# Accelerometre.net
KiCad netlist of a schematic drawn in Altium Designer
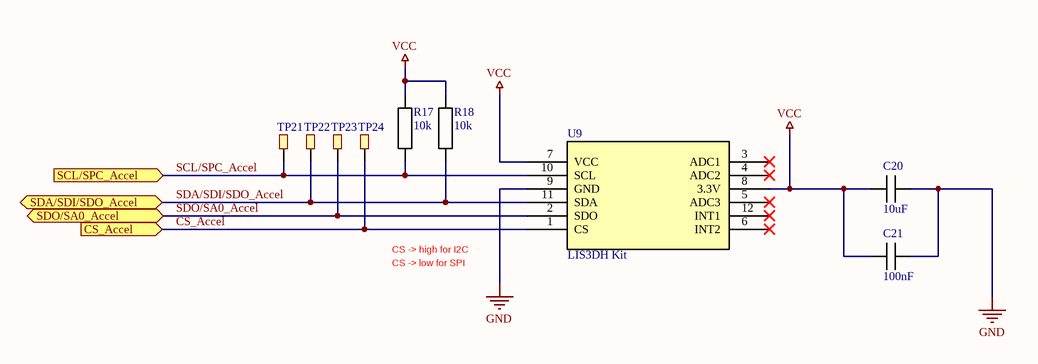
[diagram p0: Accelerometre.SchDoc]

(export (version "E")
  (design (tool "Eeschema 10.0.6"))
  (components
    (comp (ref "C20")
      (value "10uF")
      (footprint "CAPC1608X08M")
      (description "CAPC 10uF X5R 10V 20% 1608 (0603 INCH)")
      (fields (field (name "TOLERANCE") "±20%") (field (name "MANUFACTURER") "TDK"))
      (libsource (lib "ETML-ES") (part "CAP"))
    )
    (comp (ref "C21")
      (value "100nF")
      (footprint "CAPC1608X08M")
      (description "CAPC 100nF X7R 50V 10% 1608 (0603 INCH)")
      (fields (field (name "VOLTAGE") "50V") (field (name "MANUFACTURER") "TDK"))
      (libsource (lib "ETML-ES") (part "CAP"))
    )
    (comp (ref "R17")
      (value "10k")
      (footprint "RESC1608X06M")
      (description "RES 10kohm  ±1% 0.1W  1608 (0603 INCH)")
      (fields (field (name "TOLERANCE") "±1%") (field (name "VOLTAGE") "75V"))
      (libsource (lib "ETML-ES") (part "RES"))
    )
    (comp (ref "R18")
      (value "10k")
      (footprint "RESC1608X06M")
      (description "RES 10kohm  ±1% 0.1W  1608 (0603 INCH)")
      (fields (field (name "TOLERANCE") "±1%") (field (name "VOLTAGE") "75V"))
      (libsource (lib "ETML-ES") (part "RES"))
    )
    (comp (ref "TP21")
      (value "TestPoint")
      (footprint "KEYSTONE_5019")
      (libsource (lib "Schlib1") (part "TestPoint"))
    )
    (comp (ref "TP22")
      (value "TestPoint")
      (footprint "KEYSTONE_5019")
      (libsource (lib "Schlib1") (part "TestPoint"))
    )
    (comp (ref "TP23")
      (value "TestPoint")
      (footprint "KEYSTONE_5019")
      (libsource (lib "Schlib1") (part "TestPoint"))
    )
    (comp (ref "TP24")
      (value "TestPoint")
      (footprint "KEYSTONE_5019")
      (libsource (lib "Schlib1") (part "TestPoint"))
    )
    (comp (ref "U9")
      (value "LIS3DH Kit")
      (footprint "LIS3DH_Kit")
      (libsource (lib "Schlib1") (part "LIS3DH Kit"))
    )
  )
  (nets
    (net (code "1") (name "/CS_Accel") (class "Default")
      (node (ref "TP24") (pin "1") (pinfunction "1_1") (pintype "passive"))
      (node (ref "U9") (pin "1") (pinfunction "CS_1") (pintype "passive"))
    )
    (net (code "2") (name "/SCL{slash}SPC_Accel") (class "Default")
      (node (ref "R17") (pin "1") (pinfunction "1_1") (pintype "passive"))
      (node (ref "TP21") (pin "1") (pinfunction "1_1") (pintype "passive"))
      (node (ref "U9") (pin "10") (pinfunction "SCL_10") (pintype "passive"))
    )
    (net (code "3") (name "/SDA{slash}SDI{slash}SDO_Accel") (class "Default")
      (node (ref "R18") (pin "1") (pinfunction "1_1") (pintype "passive"))
      (node (ref "TP22") (pin "1") (pinfunction "1_1") (pintype "passive"))
      (node (ref "U9") (pin "11") (pinfunction "SDA_11") (pintype "passive"))
    )
    (net (code "4") (name "/SDO{slash}SA0_Accel") (class "Default")
      (node (ref "TP23") (pin "1") (pinfunction "1_1") (pintype "passive"))
      (node (ref "U9") (pin "2") (pinfunction "SDO_2") (pintype "passive"))
    )
    (net (code "5") (name "GND") (class "Default")
      (node (ref "C20") (pin "2") (pinfunction "2_2") (pintype "passive"))
      (node (ref "C21") (pin "2") (pinfunction "2_2") (pintype "passive"))
      (node (ref "U9") (pin "9") (pinfunction "GND_9") (pintype "passive"))
    )
    (net (code "6") (name "VCC") (class "Default")
      (node (ref "C20") (pin "1") (pinfunction "1_1") (pintype "passive"))
      (node (ref "C21") (pin "1") (pinfunction "1_1") (pintype "passive"))
      (node (ref "R17") (pin "2") (pinfunction "2_2") (pintype "passive"))
      (node (ref "R18") (pin "2") (pinfunction "2_2") (pintype "passive"))
      (node (ref "U9") (pin "7") (pinfunction "VCC_7") (pintype "passive"))
      (node (ref "U9") (pin "8") (pinfunction "3.3V_8") (pintype "passive"))
    )
    (net (code "7") (name "unconnected-(U9-ADC1-Pad3)") (class "Default")
      (node (ref "U9") (pin "3") (pinfunction "ADC1_3") (pintype "passive+no_connect"))
    )
    (net (code "8") (name "unconnected-(U9-ADC2-Pad4)") (class "Default")
      (node (ref "U9") (pin "4") (pinfunction "ADC2_4") (pintype "passive+no_connect"))
    )
    (net (code "9") (name "unconnected-(U9-ADC3-Pad5)") (class "Default")
      (node (ref "U9") (pin "5") (pinfunction "ADC3_5") (pintype "power_in+no_connect"))
    )
    (net (code "10") (name "unconnected-(U9-INT1-Pad12)") (class "Default")
      (node (ref "U9") (pin "12") (pinfunction "INT1_12") (pintype "power_in+no_connect"))
    )
    (net (code "11") (name "unconnected-(U9-INT2-Pad6)") (class "Default")
      (node (ref "U9") (pin "6") (pinfunction "INT2_6") (pintype "passive+no_connect"))
    )
  )
)
